# Thermocouple.net
KiCad netlist of a schematic drawn in EAGLE
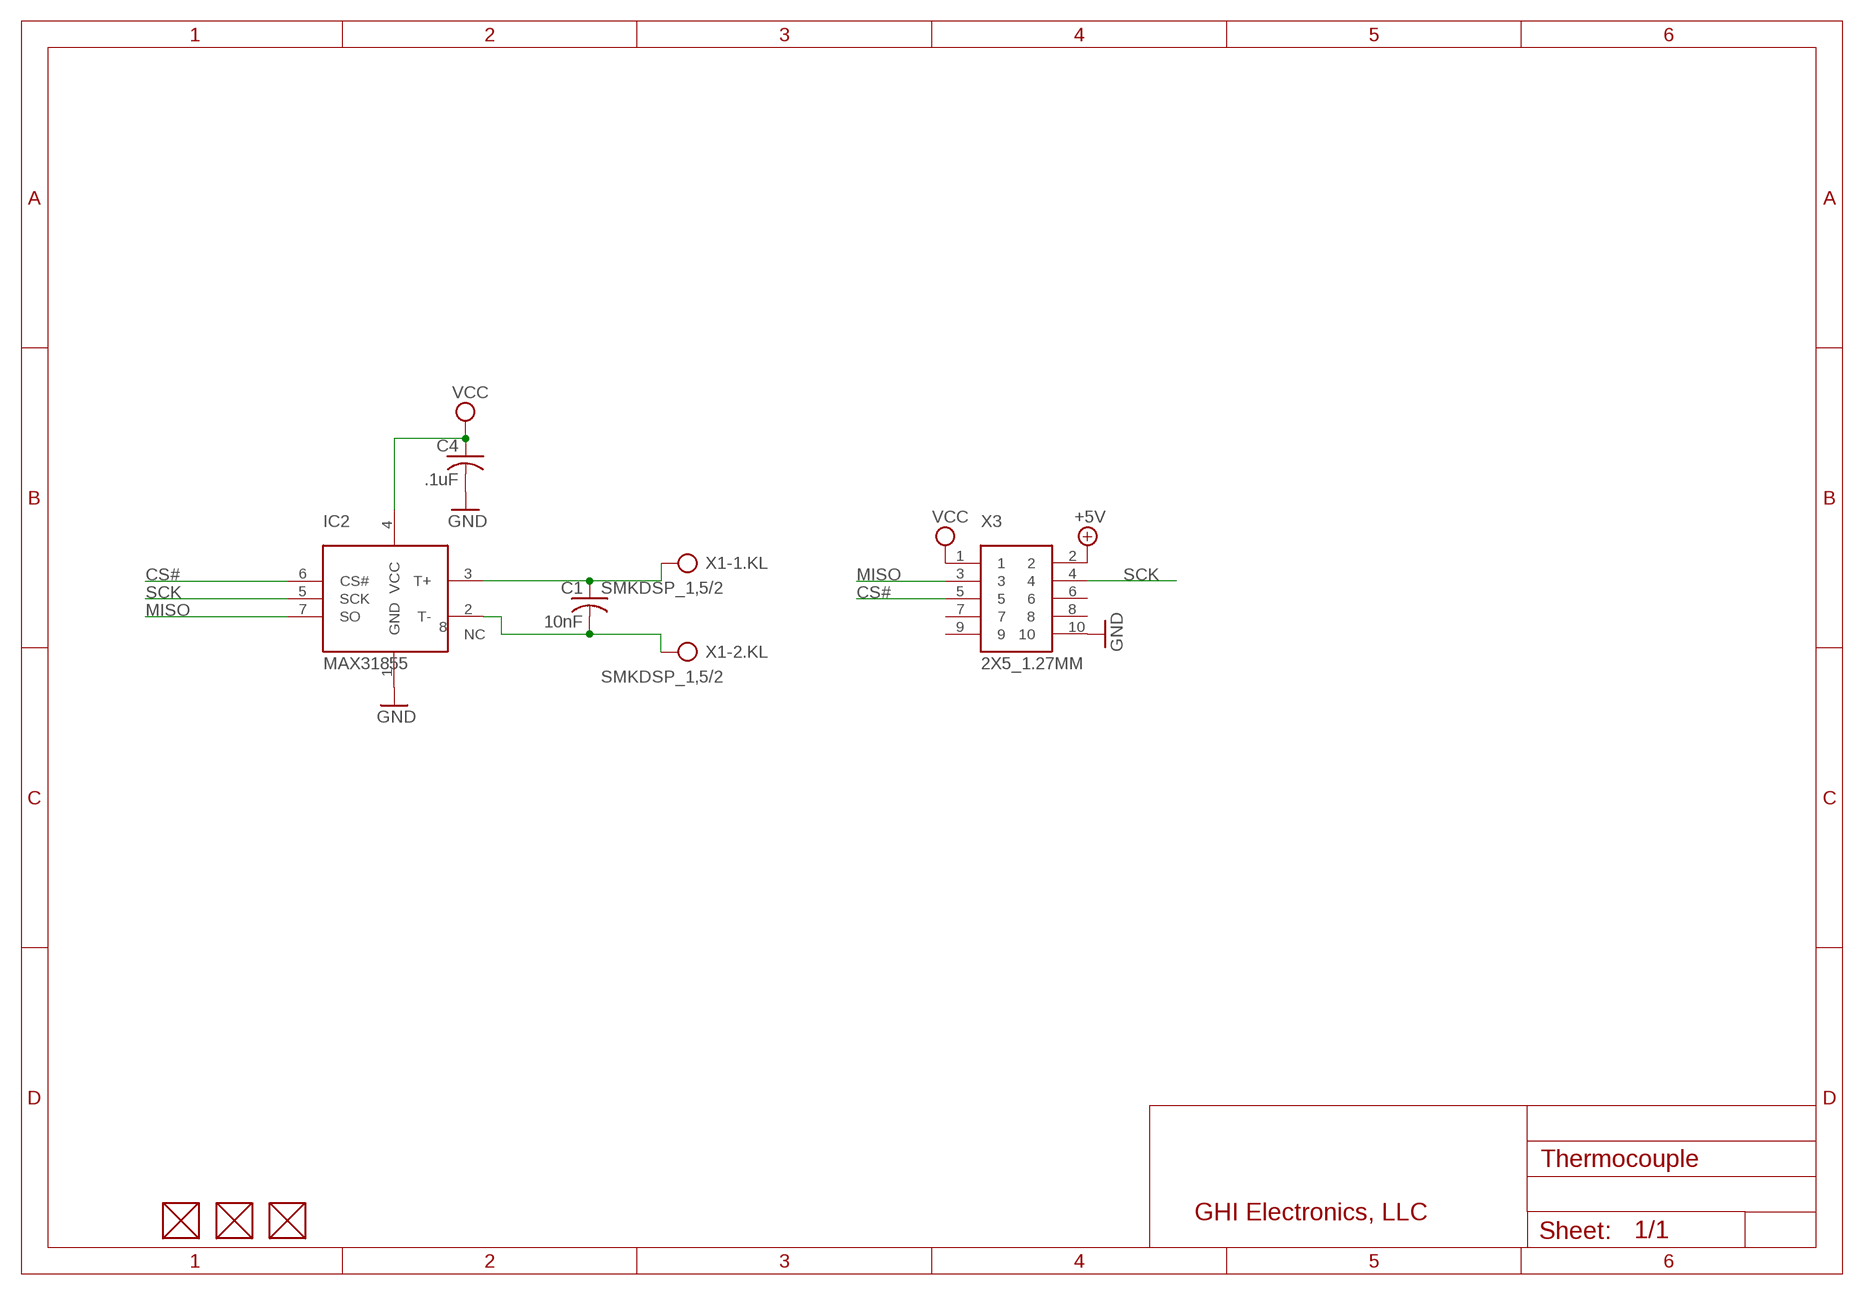
[diagram p0: schematic, sheet 1]

(export (version "E")
  (design (tool "Eeschema 10.0.6"))
  (components
    (comp (ref "C1")
      (value "10nF")
      (footprint "eagle-import:C0603K")
      (libsource (lib "eagle-import") (part "C-USC0603K"))
    )
    (comp (ref "C4")
      (value ".1uF")
      (footprint "eagle-import:C0603K")
      (libsource (lib "eagle-import") (part "C-USC0603K"))
    )
    (comp (ref "FUD1")
      (value "FIDUCIAL")
      (footprint "eagle-import:FIDUCIAL_40MIL")
      (libsource (lib "eagle-import") (part "FIDUCIAL"))
    )
    (comp (ref "FUD2")
      (value "FIDUCIAL")
      (footprint "eagle-import:FIDUCIAL_40MIL")
      (libsource (lib "eagle-import") (part "FIDUCIAL"))
    )
    (comp (ref "FUD3")
      (value "FIDUCIAL")
      (footprint "eagle-import:FIDUCIAL_40MIL")
      (libsource (lib "eagle-import") (part "FIDUCIAL"))
    )
    (comp (ref "IC2")
      (value "MAX31855")
      (footprint "eagle-import:SO8")
      (libsource (lib "eagle-import") (part "MAX6675"))
    )
    (comp (ref "X1")
      (value "SMKDSP_1,5/2")
      (footprint "eagle-import:SMKDSP_1,5_2")
      (libsource (lib "eagle-import") (part "SMKDSP_1,5/2"))
    )
    (comp (ref "X3")
      (value "2X5_1.27MM")
      (footprint "eagle-import:2X5_1.27MM")
      (libsource (lib "eagle-import") (part "2X5_1.27MM"))
    )
  )
  (nets
    (net (code "1") (name "+5V") (class "Default")
      (node (ref "X3") (pin "2") (pinfunction "2_2") (pintype "bidirectional"))
    )
    (net (code "2") (name "/CS#") (class "Default")
      (node (ref "IC2") (pin "6") (pinfunction "CS#_6") (pintype "bidirectional"))
      (node (ref "X3") (pin "5") (pinfunction "5_5") (pintype "bidirectional"))
    )
    (net (code "3") (name "/MISO") (class "Default")
      (node (ref "IC2") (pin "7") (pinfunction "SO_7") (pintype "bidirectional"))
      (node (ref "X3") (pin "3") (pinfunction "3_3") (pintype "bidirectional"))
    )
    (net (code "4") (name "/SCK") (class "Default")
      (node (ref "IC2") (pin "5") (pinfunction "SCK_5") (pintype "bidirectional"))
      (node (ref "X3") (pin "4") (pinfunction "4_4") (pintype "bidirectional"))
    )
    (net (code "5") (name "GND") (class "Default")
      (node (ref "C4") (pin "2") (pinfunction "2_2") (pintype "passive"))
      (node (ref "IC2") (pin "1") (pinfunction "GND_1") (pintype "bidirectional"))
      (node (ref "X3") (pin "10") (pinfunction "10_10") (pintype "bidirectional"))
    )
    (net (code "6") (name "Net-(IC2-T+)") (class "Default")
      (node (ref "C1") (pin "1") (pinfunction "1_1") (pintype "passive"))
      (node (ref "IC2") (pin "3") (pinfunction "T+_3") (pintype "bidirectional"))
      (node (ref "X1") (pin "1") (pinfunction "KL_1") (pintype "passive"))
    )
    (net (code "7") (name "Net-(IC2-T-)") (class "Default")
      (node (ref "C1") (pin "2") (pinfunction "2_2") (pintype "passive"))
      (node (ref "IC2") (pin "2") (pinfunction "T-_2") (pintype "bidirectional"))
      (node (ref "X1") (pin "2") (pinfunction "KL_2") (pintype "passive"))
    )
    (net (code "8") (name "VCC") (class "Default")
      (node (ref "C4") (pin "1") (pinfunction "1_1") (pintype "passive"))
      (node (ref "IC2") (pin "4") (pinfunction "VCC_4") (pintype "bidirectional"))
      (node (ref "X3") (pin "1") (pinfunction "1_1") (pintype "bidirectional"))
    )
    (net (code "9") (name "unconnected-(FUD1-PadP$1)") (class "Default")
      (node (ref "FUD1") (pin "P$1") (pinfunction "P$1_P$1") (pintype "no_connect"))
    )
    (net (code "10") (name "unconnected-(FUD2-PadP$1)") (class "Default")
      (node (ref "FUD2") (pin "P$1") (pinfunction "P$1_P$1") (pintype "no_connect"))
    )
    (net (code "11") (name "unconnected-(FUD3-PadP$1)") (class "Default")
      (node (ref "FUD3") (pin "P$1") (pinfunction "P$1_P$1") (pintype "no_connect"))
    )
    (net (code "12") (name "unconnected-(IC2-NC-Pad8)") (class "Default")
      (node (ref "IC2") (pin "8") (pinfunction "NC_8") (pintype "bidirectional"))
    )
    (net (code "13") (name "unconnected-(X3-Pad6)") (class "Default")
      (node (ref "X3") (pin "6") (pinfunction "6_6") (pintype "bidirectional"))
    )
    (net (code "14") (name "unconnected-(X3-Pad7)") (class "Default")
      (node (ref "X3") (pin "7") (pinfunction "7_7") (pintype "bidirectional"))
    )
    (net (code "15") (name "unconnected-(X3-Pad8)") (class "Default")
      (node (ref "X3") (pin "8") (pinfunction "8_8") (pintype "bidirectional"))
    )
    (net (code "16") (name "unconnected-(X3-Pad9)") (class "Default")
      (node (ref "X3") (pin "9") (pinfunction "9_9") (pintype "bidirectional"))
    )
  )
)
